# VoltageSourcePCBFINAL.net
KiCad netlist of a schematic drawn in EAGLE
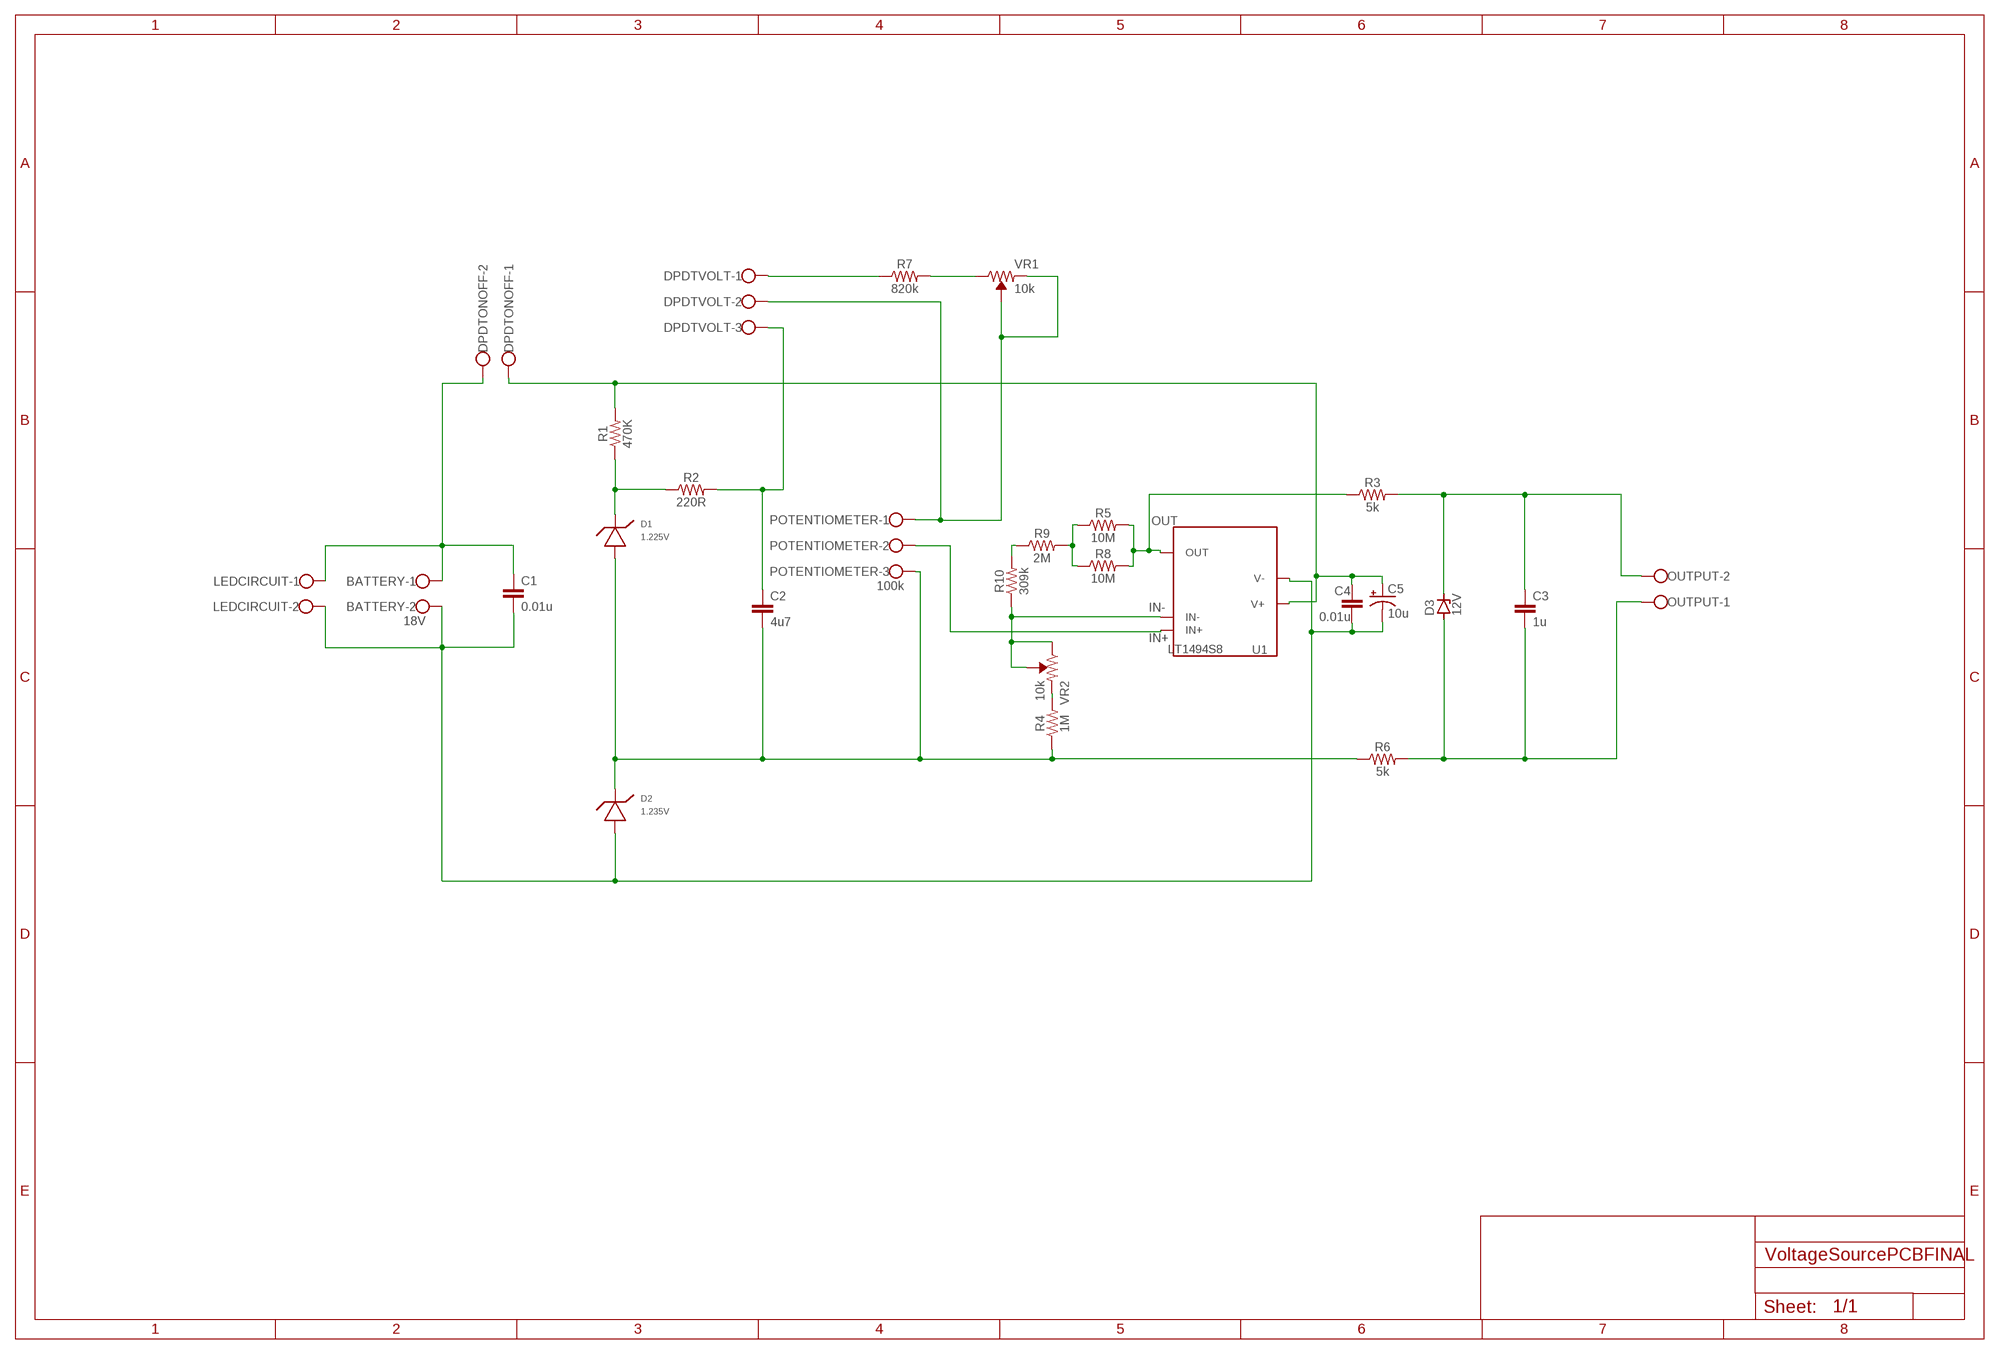
[diagram p0: schematic, sheet 1]

(export (version "E")
  (design (tool "Eeschema 10.0.6"))
  (components
    (comp (ref "BATTERY")
      (value "18V")
      (footprint "eagle-import:W237-102")
      (fields (field (name "MPN") "237-102"))
      (libsource (lib "eagle-import") (part "W237-102"))
    )
    (comp (ref "C1")
      (value "0.01u")
      (footprint "eagle-import:0805")
      (libsource (lib "eagle-import") (part "0.33UF/330NF-0805-50V-10%"))
    )
    (comp (ref "C2")
      (value "4u7")
      (footprint "eagle-import:0805")
      (libsource (lib "eagle-import") (part "0.33UF/330NF-0805-50V-10%"))
    )
    (comp (ref "C3")
      (value "1u")
      (footprint "eagle-import:0805")
      (libsource (lib "eagle-import") (part "0.33UF/330NF-0805-50V-10%"))
    )
    (comp (ref "C4")
      (value "0.01u")
      (footprint "eagle-import:0805")
      (libsource (lib "eagle-import") (part "0.33UF/330NF-0805-50V-10%"))
    )
    (comp (ref "C5")
      (value "10u")
      (footprint "eagle-import:EIA7343")
      (libsource (lib "eagle-import") (part "100UF-POLAR-EIA7343-10V-10%(TANT)"))
    )
    (comp (ref "D1")
      (value "1.225V")
      (footprint "eagle-import:S8PACKAGE")
      (libsource (lib "eagle-import") (part "LT1004CS8SMD"))
    )
    (comp (ref "D2")
      (value "1.235V")
      (footprint "eagle-import:SOIC-8PACKAGE")
      (libsource (lib "eagle-import") (part "LM385BDSMD"))
    )
    (comp (ref "D3")
      (value "12V")
      (footprint "eagle-import:SOT23")
      (libsource (lib "eagle-import") (part "ZENER-DIODESOT23"))
    )
    (comp (ref "DPDTONOFF")
      (value "W237-102")
      (footprint "eagle-import:W237-102")
      (fields (field (name "MPN") "237-102"))
      (libsource (lib "eagle-import") (part "W237-102"))
    )
    (comp (ref "DPDTVOLT")
      (value "W237-103")
      (footprint "eagle-import:W237-103")
      (fields (field (name "MPN") "237-103"))
      (libsource (lib "eagle-import") (part "W237-103"))
    )
    (comp (ref "LEDCIRCUIT")
      (value "W237-102")
      (footprint "eagle-import:W237-102")
      (fields (field (name "MPN") "237-102"))
      (libsource (lib "eagle-import") (part "W237-102"))
    )
    (comp (ref "OUTPUT")
      (value "W237-102")
      (footprint "eagle-import:W237-102")
      (fields (field (name "MPN") "237-102"))
      (libsource (lib "eagle-import") (part "W237-102"))
    )
    (comp (ref "POTENTIOMETER")
      (value "100k")
      (footprint "eagle-import:W237-103")
      (fields (field (name "MPN") "237-103"))
      (libsource (lib "eagle-import") (part "W237-103"))
    )
    (comp (ref "R1")
      (value "470K")
      (footprint "eagle-import:0805")
      (libsource (lib "eagle-import") (part "RESISTOR0805"))
    )
    (comp (ref "R2")
      (value "220R")
      (footprint "eagle-import:0805")
      (libsource (lib "eagle-import") (part "RESISTOR0805"))
    )
    (comp (ref "R3")
      (value "5k")
      (footprint "eagle-import:0805")
      (libsource (lib "eagle-import") (part "RESISTOR0805"))
    )
    (comp (ref "R4")
      (value "1M")
      (footprint "eagle-import:0805")
      (libsource (lib "eagle-import") (part "RESISTOR0805"))
    )
    (comp (ref "R5")
      (value "10M")
      (footprint "eagle-import:0805")
      (libsource (lib "eagle-import") (part "RESISTOR0805"))
    )
    (comp (ref "R6")
      (value "5k")
      (footprint "eagle-import:0805")
      (libsource (lib "eagle-import") (part "RESISTOR0805"))
    )
    (comp (ref "R7")
      (value "820k")
      (footprint "eagle-import:0805")
      (libsource (lib "eagle-import") (part "RESISTOR0805"))
    )
    (comp (ref "R8")
      (value "10M")
      (footprint "eagle-import:0805")
      (libsource (lib "eagle-import") (part "RESISTOR0805"))
    )
    (comp (ref "R9")
      (value "2M")
      (footprint "eagle-import:0805")
      (libsource (lib "eagle-import") (part "RESISTOR0805"))
    )
    (comp (ref "R10")
      (value "309k")
      (footprint "eagle-import:0805")
      (libsource (lib "eagle-import") (part "RESISTOR0805"))
    )
    (comp (ref "U1")
      (value "LT1494S8")
      (footprint "eagle-import:S8PACKAGE")
      (libsource (lib "eagle-import") (part "LT1494S8"))
    )
    (comp (ref "VR1")
      (value "10k")
      (footprint "eagle-import:TRIMPOT-SMD-TC33X")
      (libsource (lib "eagle-import") (part "TRIMPOT-SMD-3MM-OPEN-1/10W-25%"))
    )
    (comp (ref "VR2")
      (value "10k")
      (footprint "eagle-import:TRIMPOT-SMD-TC33X")
      (libsource (lib "eagle-import") (part "TRIMPOT-SMD-3MM-OPEN-1/10W-25%"))
    )
  )
  (nets
    (net (code "1") (name "/IN+") (class "Default")
      (node (ref "POTENTIOMETER") (pin "2") (pinfunction "KL_2") (pintype "passive"))
      (node (ref "U1") (pin "3") (pinfunction "IN+_3") (pintype "input"))
    )
    (net (code "2") (name "/IN-") (class "Default")
      (node (ref "R10") (pin "1") (pinfunction "1_1") (pintype "passive"))
      (node (ref "U1") (pin "2") (pinfunction "IN-_2") (pintype "input"))
      (node (ref "VR2") (pin "1") (pinfunction "CW_1") (pintype "passive"))
      (node (ref "VR2") (pin "2") (pinfunction "WIPER_2") (pintype "passive"))
    )
    (net (code "3") (name "/OUT") (class "Default")
      (node (ref "R3") (pin "1") (pinfunction "1_1") (pintype "passive"))
      (node (ref "R5") (pin "2") (pinfunction "2_2") (pintype "passive"))
      (node (ref "R8") (pin "2") (pinfunction "2_2") (pintype "passive"))
      (node (ref "U1") (pin "6") (pinfunction "OUT_6") (pintype "output"))
    )
    (net (code "4") (name "Net-(BATTERYA-KL)") (class "Default")
      (node (ref "BATTERY") (pin "1") (pinfunction "KL_1") (pintype "passive"))
      (node (ref "C1") (pin "1") (pinfunction "1_1") (pintype "passive"))
      (node (ref "DPDTONOFF") (pin "2") (pinfunction "KL_2") (pintype "passive"))
      (node (ref "LEDCIRCUIT") (pin "1") (pinfunction "KL_1") (pintype "passive"))
    )
    (net (code "5") (name "Net-(BATTERYB-KL)") (class "Default")
      (node (ref "BATTERY") (pin "2") (pinfunction "KL_2") (pintype "passive"))
      (node (ref "C1") (pin "2") (pinfunction "2_2") (pintype "passive"))
      (node (ref "C4") (pin "2") (pinfunction "2_2") (pintype "passive"))
      (node (ref "C5") (pin "C") (pinfunction "-_C") (pintype "passive"))
      (node (ref "D2") (pin "4") (pinfunction "ANODE_4") (pintype "bidirectional"))
      (node (ref "LEDCIRCUIT") (pin "2") (pinfunction "KL_2") (pintype "passive"))
      (node (ref "U1") (pin "4") (pinfunction "V-_4") (pintype "power_in"))
    )
    (net (code "6") (name "Net-(C5-+)") (class "Default")
      (node (ref "C4") (pin "1") (pinfunction "1_1") (pintype "passive"))
      (node (ref "C5") (pin "A") (pinfunction "+_A") (pintype "passive"))
      (node (ref "DPDTONOFF") (pin "1") (pinfunction "KL_1") (pintype "passive"))
      (node (ref "R1") (pin "2") (pinfunction "2_2") (pintype "passive"))
      (node (ref "U1") (pin "7") (pinfunction "V+_7") (pintype "power_in"))
    )
    (net (code "7") (name "Net-(D1-ANODE)") (class "Default")
      (node (ref "C2") (pin "2") (pinfunction "2_2") (pintype "passive"))
      (node (ref "D1") (pin "4") (pinfunction "ANODE_4") (pintype "bidirectional"))
      (node (ref "D2") (pin "8") (pinfunction "CATHODE_8") (pintype "bidirectional"))
      (node (ref "POTENTIOMETER") (pin "3") (pinfunction "KL_3") (pintype "passive"))
      (node (ref "R4") (pin "1") (pinfunction "1_1") (pintype "passive"))
      (node (ref "R6") (pin "1") (pinfunction "1_1") (pintype "passive"))
    )
    (net (code "8") (name "Net-(D1-CATHODE-Pad6)") (class "Default")
      (node (ref "D1") (pin "6") (pinfunction "CATHODE_6") (pintype "bidirectional"))
      (node (ref "D1") (pin "8") (pinfunction "CATHODE_8") (pintype "bidirectional"))
      (node (ref "R1") (pin "1") (pinfunction "1_1") (pintype "passive"))
      (node (ref "R2") (pin "1") (pinfunction "1_1") (pintype "passive"))
    )
    (net (code "9") (name "Net-(D3-A)") (class "Default")
      (node (ref "C3") (pin "2") (pinfunction "2_2") (pintype "passive"))
      (node (ref "D3") (pin "1") (pinfunction "A_1") (pintype "passive"))
      (node (ref "OUTPUT") (pin "1") (pinfunction "KL_1") (pintype "passive"))
      (node (ref "R6") (pin "2") (pinfunction "2_2") (pintype "passive"))
    )
    (net (code "10") (name "Net-(D3-C)") (class "Default")
      (node (ref "C3") (pin "1") (pinfunction "1_1") (pintype "passive"))
      (node (ref "D3") (pin "3") (pinfunction "C_3") (pintype "passive"))
      (node (ref "OUTPUT") (pin "2") (pinfunction "KL_2") (pintype "passive"))
      (node (ref "R3") (pin "2") (pinfunction "2_2") (pintype "passive"))
    )
    (net (code "11") (name "Net-(DPDTVOLTA-KL)") (class "Default")
      (node (ref "DPDTVOLT") (pin "1") (pinfunction "KL_1") (pintype "passive"))
      (node (ref "R7") (pin "1") (pinfunction "1_1") (pintype "passive"))
    )
    (net (code "12") (name "Net-(DPDTVOLTB-KL)") (class "Default")
      (node (ref "DPDTVOLT") (pin "2") (pinfunction "KL_2") (pintype "passive"))
      (node (ref "POTENTIOMETER") (pin "1") (pinfunction "KL_1") (pintype "passive"))
      (node (ref "VR1") (pin "2") (pinfunction "WIPER_2") (pintype "passive"))
      (node (ref "VR1") (pin "3") (pinfunction "CCW_3") (pintype "passive"))
    )
    (net (code "13") (name "Net-(DPDTVOLTC-KL)") (class "Default")
      (node (ref "C2") (pin "1") (pinfunction "1_1") (pintype "passive"))
      (node (ref "DPDTVOLT") (pin "3") (pinfunction "KL_3") (pintype "passive"))
      (node (ref "R2") (pin "2") (pinfunction "2_2") (pintype "passive"))
    )
    (net (code "14") (name "Net-(R5-Pad1)") (class "Default")
      (node (ref "R5") (pin "1") (pinfunction "1_1") (pintype "passive"))
      (node (ref "R8") (pin "1") (pinfunction "1_1") (pintype "passive"))
      (node (ref "R9") (pin "2") (pinfunction "2_2") (pintype "passive"))
    )
    (net (code "15") (name "Net-(R10-Pad2)") (class "Default")
      (node (ref "R10") (pin "2") (pinfunction "2_2") (pintype "passive"))
      (node (ref "R9") (pin "1") (pinfunction "1_1") (pintype "passive"))
    )
    (net (code "16") (name "Net-(VR1-CW)") (class "Default")
      (node (ref "R7") (pin "2") (pinfunction "2_2") (pintype "passive"))
      (node (ref "VR1") (pin "1") (pinfunction "CW_1") (pintype "passive"))
    )
    (net (code "17") (name "Net-(VR2-CCW)") (class "Default")
      (node (ref "R4") (pin "2") (pinfunction "2_2") (pintype "passive"))
      (node (ref "VR2") (pin "3") (pinfunction "CCW_3") (pintype "passive"))
    )
  )
)
